# easyMySens-Std-V2-021.net
KiCad netlist of a schematic drawn in EAGLE
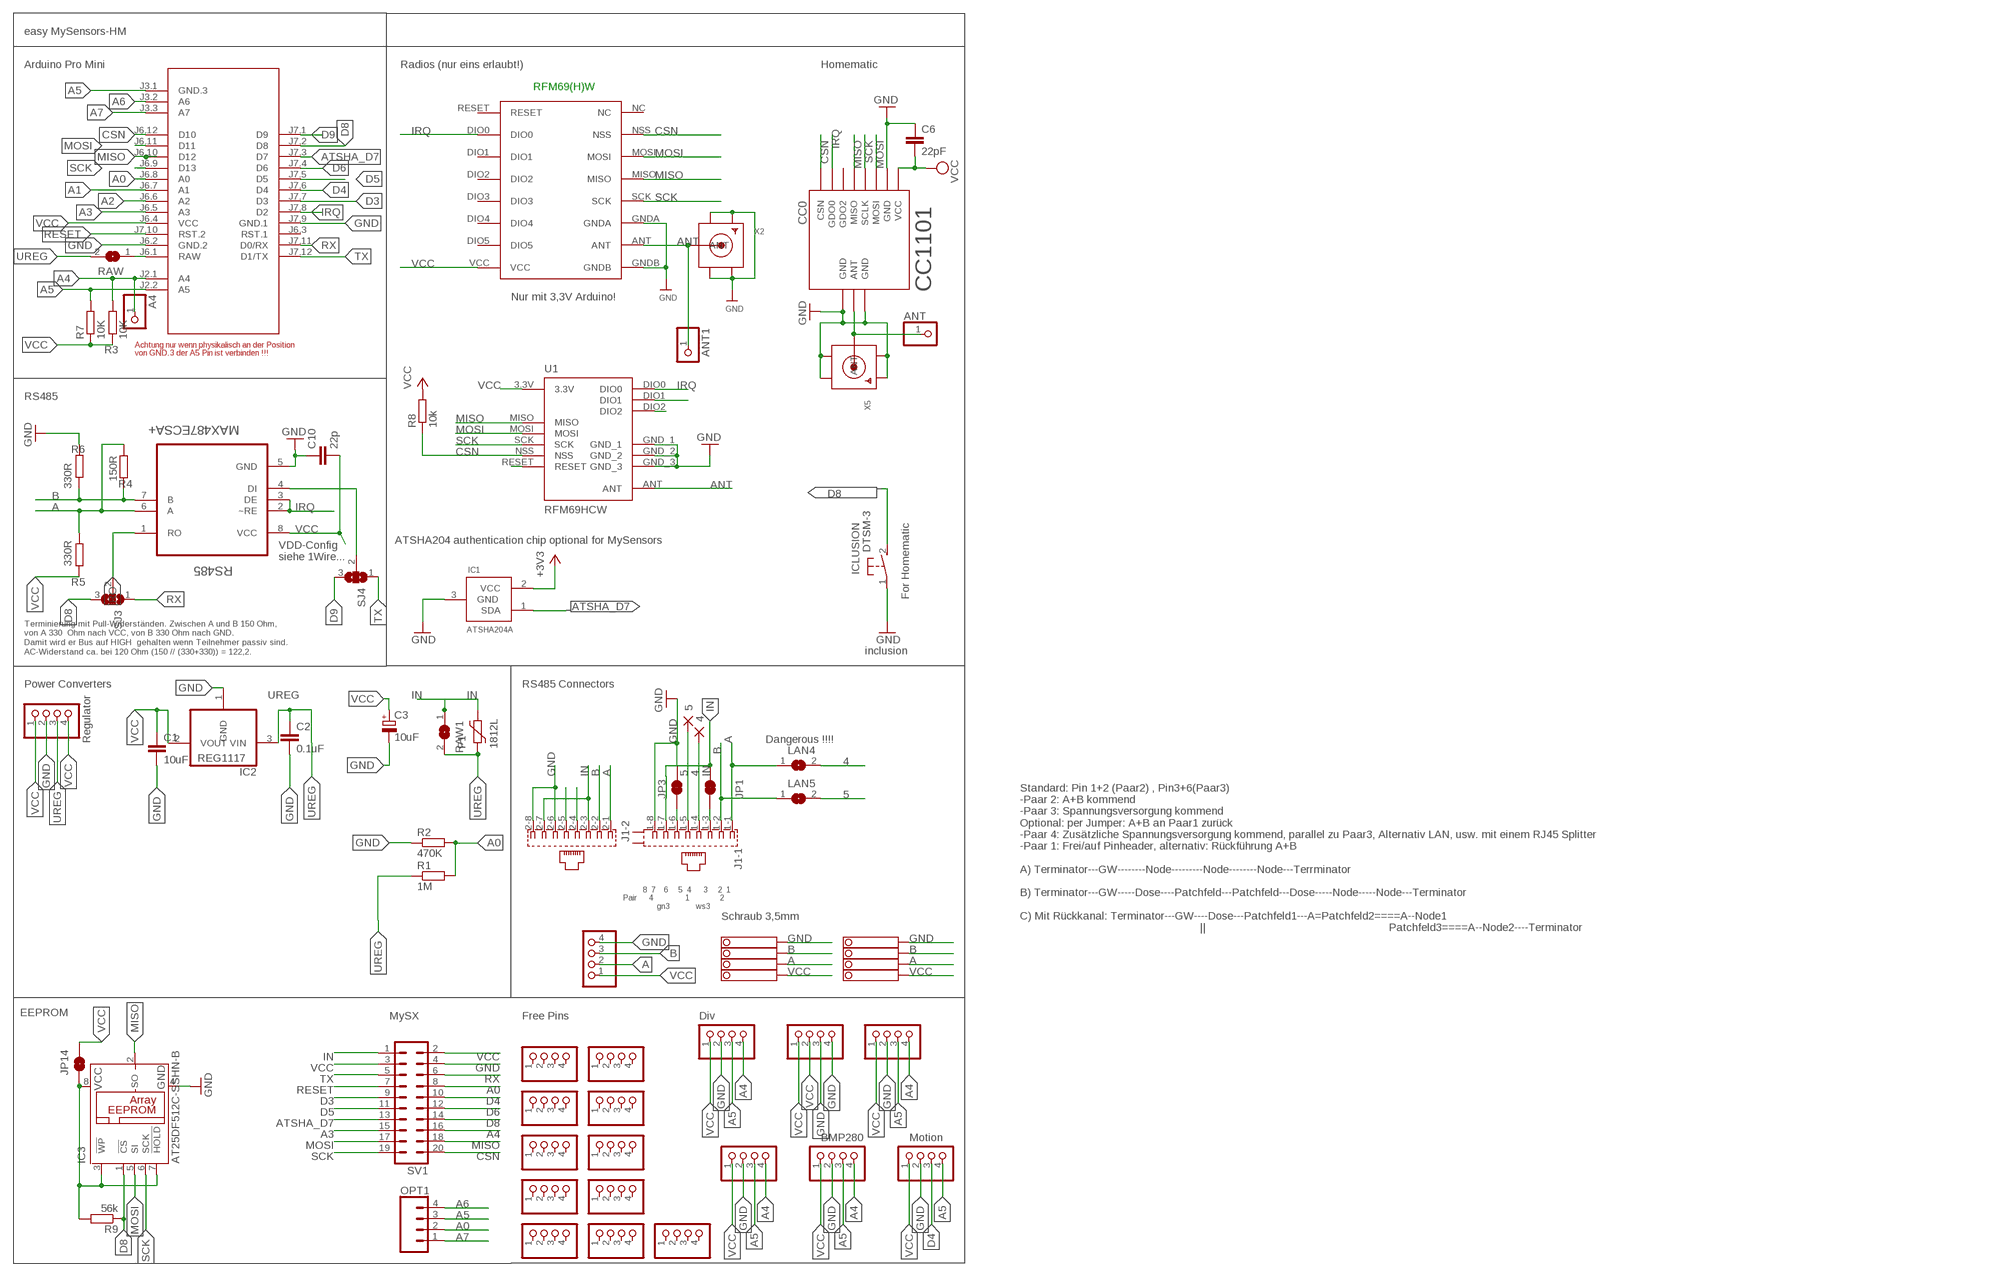
[diagram p0: schematic, sheet 1]

(export (version "E")
  (design (tool "Eeschema 10.0.6"))
  (components
    (comp (ref "4")
      (value "1,6/0,8")
      (footprint "eagle-import:1,6_0,8")
      (libsource (lib "eagle-import") (part "1,6/0,8"))
    )
    (comp (ref "5")
      (value "1,6/0,8")
      (footprint "eagle-import:1,6_0,8")
      (libsource (lib "eagle-import") (part "1,6/0,8"))
    )
    (comp (ref "A4")
      (value "PINHD-1X1")
      (footprint "eagle-import:1X01")
      (libsource (lib "eagle-import") (part "PINHD-1X1"))
    )
    (comp (ref "ANT")
      (value "PINHD-1X1")
      (footprint "eagle-import:1X01")
      (libsource (lib "eagle-import") (part "PINHD-1X1"))
    )
    (comp (ref "ANT1")
      (value "PINHD-1X1")
      (footprint "eagle-import:1X01")
      (libsource (lib "eagle-import") (part "PINHD-1X1"))
    )
    (comp (ref "BH1750")
      (value "PINHD-1X04_2.54-S")
      (footprint "eagle-import:1X04-S")
      (libsource (lib "eagle-import") (part "PINHD-1X04_2.54-S"))
    )
    (comp (ref "C1")
      (value "10uF")
      (footprint "eagle-import:C1210")
      (libsource (lib "eagle-import") (part "C-EUC1210"))
    )
    (comp (ref "C2")
      (value "0.1uF")
      (footprint "eagle-import:C1206")
      (libsource (lib "eagle-import") (part "C-EUC1206"))
    )
    (comp (ref "C3")
      (value "10uF")
      (footprint "eagle-import:SMC_C")
      (libsource (lib "eagle-import") (part "CPOL-EUSMCC"))
    )
    (comp (ref "C6")
      (value "22pF")
      (footprint "eagle-import:C0805")
      (libsource (lib "eagle-import") (part "C-EUC0805"))
    )
    (comp (ref "C10")
      (value "22p")
      (footprint "eagle-import:C0805")
      (libsource (lib "eagle-import") (part "C-EUC0805"))
    )
    (comp (ref "CC0")
      (value "CC1101")
      (footprint "eagle-import:CC1101_MODULE1_SMD")
      (libsource (lib "eagle-import") (part "CC1101_MODULE1SMD"))
    )
    (comp (ref "F1")
      (value "1812L")
      (footprint "eagle-import:1812L")
      (libsource (lib "eagle-import") (part "1812L"))
    )
    (comp (ref "I2C-1")
      (value "PINHD-1X04_2.54-S")
      (footprint "eagle-import:1X04-S")
      (libsource (lib "eagle-import") (part "PINHD-1X04_2.54-S"))
    )
    (comp (ref "I2C-2")
      (value "PINHD-1X04_2.54-S")
      (footprint "eagle-import:1X04-S")
      (libsource (lib "eagle-import") (part "PINHD-1X04_2.54-S"))
    )
    (comp (ref "I2C-3")
      (value "PINHD-1X04_2.54-S")
      (footprint "eagle-import:1X04-S")
      (libsource (lib "eagle-import") (part "PINHD-1X04_2.54-S"))
    )
    (comp (ref "I2C-4")
      (value "PINHD-1X04_2.54-S")
      (footprint "eagle-import:1X04-S")
      (libsource (lib "eagle-import") (part "PINHD-1X04_2.54-S"))
    )
    (comp (ref "IC1")
      (value "ATSHA204A")
      (footprint "eagle-import:SOT23")
      (libsource (lib "eagle-import") (part "ATSHA204A"))
    )
    (comp (ref "IC2")
      (value "REG1117")
      (footprint "eagle-import:SOT223")
      (libsource (lib "eagle-import") (part "REG1117"))
    )
    (comp (ref "IC3")
      (value "AT25DF512C-SSHN-B")
      (footprint "eagle-import:SO-08")
      (fields (field (name "MF") "MICROCHIP") (field (name "MPN") "25AA080/SN"))
      (libsource (lib "eagle-import") (part "25SNAA080"))
    )
    (comp (ref "ICLUSION")
      (value "DTSM-3")
      (footprint "eagle-import:DTSM-3")
      (libsource (lib "eagle-import") (part "DTSM-3"))
    )
    (comp (ref "J1")
      (value "557570-1")
      (footprint "eagle-import:557570-1")
      (libsource (lib "eagle-import") (part "557570-1"))
    )
    (comp (ref "JP1")
      (value "JUMPER-SMT_2_NC_TRACE_SILK")
      (footprint "eagle-import:SMT-JUMPER_2_NC_TRACE_SILK")
      (libsource (lib "eagle-import") (part "JUMPER-SMT_2_NC_TRACE_SILK"))
    )
    (comp (ref "JP2")
      (value "PINHD-1X04_2.54-S")
      (footprint "eagle-import:1X04-S")
      (libsource (lib "eagle-import") (part "PINHD-1X04_2.54-S"))
    )
    (comp (ref "JP3")
      (value "JUMPER-SMT_2_NC_TRACE_SILK")
      (footprint "eagle-import:SMT-JUMPER_2_NC_TRACE_SILK")
      (libsource (lib "eagle-import") (part "JUMPER-SMT_2_NC_TRACE_SILK"))
    )
    (comp (ref "JP4")
      (value "PINHD-1X04_2.54-S")
      (footprint "eagle-import:1X04-S")
      (libsource (lib "eagle-import") (part "PINHD-1X04_2.54-S"))
    )
    (comp (ref "JP5")
      (value "PINHD-1X04_2.54-S")
      (footprint "eagle-import:1X04-S")
      (libsource (lib "eagle-import") (part "PINHD-1X04_2.54-S"))
    )
    (comp (ref "JP6")
      (value "PINHD-1X04_2.54-S")
      (footprint "eagle-import:1X04-S")
      (libsource (lib "eagle-import") (part "PINHD-1X04_2.54-S"))
    )
    (comp (ref "JP7")
      (value "PINHD-1X04_2.54-S")
      (footprint "eagle-import:1X04-S")
      (libsource (lib "eagle-import") (part "PINHD-1X04_2.54-S"))
    )
    (comp (ref "JP8")
      (value "PINHD-1X04_2.54-S")
      (footprint "eagle-import:1X04-S")
      (libsource (lib "eagle-import") (part "PINHD-1X04_2.54-S"))
    )
    (comp (ref "JP9")
      (value "PINHD-1X04_2.54-S")
      (footprint "eagle-import:1X04-S")
      (libsource (lib "eagle-import") (part "PINHD-1X04_2.54-S"))
    )
    (comp (ref "JP10")
      (value "PINHD-1X04_2.54-S")
      (footprint "eagle-import:1X04-S")
      (libsource (lib "eagle-import") (part "PINHD-1X04_2.54-S"))
    )
    (comp (ref "JP11")
      (value "PINHD-1X04_2.54-S")
      (footprint "eagle-import:1X04-S")
      (libsource (lib "eagle-import") (part "PINHD-1X04_2.54-S"))
    )
    (comp (ref "JP12")
      (value "PINHD-1X04_2.54-S")
      (footprint "eagle-import:1X04-S")
      (libsource (lib "eagle-import") (part "PINHD-1X04_2.54-S"))
    )
    (comp (ref "JP13")
      (value "PINHD-1X04_2.54-S")
      (footprint "eagle-import:1X04-S")
      (libsource (lib "eagle-import") (part "PINHD-1X04_2.54-S"))
    )
    (comp (ref "JP14")
      (value "JUMPER-SMT_2_NC_TRACE_SILK")
      (footprint "eagle-import:SMT-JUMPER_2_NC_TRACE_SILK")
      (libsource (lib "eagle-import") (part "JUMPER-SMT_2_NC_TRACE_SILK"))
    )
    (comp (ref "LAN4")
      (value "SJ")
      (footprint "eagle-import:SJ")
      (libsource (lib "eagle-import") (part "SJ"))
    )
    (comp (ref "LAN5")
      (value "SJ")
      (footprint "eagle-import:SJ")
      (libsource (lib "eagle-import") (part "SJ"))
    )
    (comp (ref "M1")
      (value "ARDUINO-PRO-MINI-3.3V#NP")
      (footprint "eagle-import:ARDUINO-PRO-MINI#NP")
      (libsource (lib "eagle-import") (part "ARDUINO-PRO-MINI-#NP3.3V"))
    )
    (comp (ref "MOTION")
      (value "PINHD-1X04_2.54-S")
      (footprint "eagle-import:1X04-S")
      (libsource (lib "eagle-import") (part "PINHD-1X04_2.54-S"))
    )
    (comp (ref "OPT1")
      (value "CONN_04")
      (footprint "eagle-import:1X04")
      (libsource (lib "eagle-import") (part "CONN_04"))
    )
    (comp (ref "R1")
      (value "1M")
      (footprint "eagle-import:R0805")
      (libsource (lib "eagle-import") (part "R-EU_R0805"))
    )
    (comp (ref "R2")
      (value "470K")
      (footprint "eagle-import:R0805")
      (libsource (lib "eagle-import") (part "R-EU_R0805"))
    )
    (comp (ref "R3")
      (value "10K")
      (footprint "eagle-import:R0805")
      (libsource (lib "eagle-import") (part "R-EU_R0805"))
    )
    (comp (ref "R4")
      (value "150R")
      (footprint "eagle-import:R0805")
      (libsource (lib "eagle-import") (part "R-EU_R0805"))
    )
    (comp (ref "R5")
      (value "330R")
      (footprint "eagle-import:R0805")
      (libsource (lib "eagle-import") (part "R-EU_R0805"))
    )
    (comp (ref "R6")
      (value "330R")
      (footprint "eagle-import:R0805")
      (libsource (lib "eagle-import") (part "R-EU_R0805"))
    )
    (comp (ref "R7")
      (value "10K")
      (footprint "eagle-import:R0805")
      (libsource (lib "eagle-import") (part "R-EU_R0805"))
    )
    (comp (ref "R8")
      (value "10k")
      (footprint "eagle-import:M0805")
      (libsource (lib "eagle-import") (part "R-EU_M0805"))
    )
    (comp (ref "R9")
      (value "56k")
      (footprint "eagle-import:M0805")
      (libsource (lib "eagle-import") (part "resistor_R-EU_M0805"))
    )
    (comp (ref "RAW") (value "SJ") (footprint "eagle-import:SJ") (libsource (lib "eagle-import") (part "SJ")))
    (comp (ref "RAW1")
      (value "SJ")
      (footprint "eagle-import:SJ")
      (libsource (lib "eagle-import") (part "SJ"))
    )
    (comp (ref "RFM69W")
      (value "RFM69HW")
      (footprint "eagle-import:RFM")
      (libsource (lib "eagle-import") (part "RFM69HW"))
    )
    (comp (ref "RS485")
      (value "MAX487ECSA+")
      (footprint "eagle-import:SOIC127P600X175-8N")
      (libsource (lib "eagle-import") (part "MAX487ECSA+"))
    )
    (comp (ref "RS485-")
      (value "PINHD-1X04_2.54-S")
      (footprint "eagle-import:1X04-S")
      (libsource (lib "eagle-import") (part "PINHD-1X04_2.54-S"))
    )
    (comp (ref "SJ3")
      (value "SJ2W")
      (footprint "eagle-import:SJ_2")
      (libsource (lib "eagle-import") (part "SJ2W"))
    )
    (comp (ref "SJ4")
      (value "SJ2W")
      (footprint "eagle-import:SJ_2")
      (libsource (lib "eagle-import") (part "SJ2W"))
    )
    (comp (ref "STEPDWN")
      (value "PINHD-1X04_2.54-S")
      (footprint "eagle-import:1X04-S")
      (libsource (lib "eagle-import") (part "PINHD-1X04_2.54-S"))
    )
    (comp (ref "SV1")
      (value "MA10-2")
      (footprint "eagle-import:MA10-2")
      (libsource (lib "eagle-import") (part "MA10-2"))
    )
    (comp (ref "U1")
      (value "RFM69HCW")
      (footprint "eagle-import:RFM69HCW-XXXS2")
      (libsource (lib "eagle-import") (part "RFM69HCW"))
    )
    (comp (ref "X1")
      (value "1751264")
      (footprint "eagle-import:1751264")
      (libsource (lib "eagle-import") (part "1751264"))
    )
    (comp (ref "X2")
      (value "SMACONNECTOR_EDGE")
      (footprint "eagle-import:SMA_EDGELAUNCH")
      (libsource (lib "eagle-import") (part "SMACONNECTOR_EDGE"))
    )
    (comp (ref "X4")
      (value "1751264")
      (footprint "eagle-import:1751264")
      (libsource (lib "eagle-import") (part "1751264"))
    )
    (comp (ref "X5")
      (value "SMACONNECTOR_EDGE")
      (footprint "eagle-import:SMA_EDGELAUNCH")
      (libsource (lib "eagle-import") (part "SMACONNECTOR_EDGE"))
    )
  )
  (nets
    (net (code "1") (name "+3V3") (class "Default")
      (node (ref "IC1") (pin "2") (pinfunction "VCC_2") (pintype "bidirectional"))
    )
    (net (code "2") (name "/4") (class "Default")
      (node (ref "4") (pin "1") (pinfunction "P_1") (pintype "passive"))
      (node (ref "J1") (pin "1-4") (pinfunction "4_1-4") (pintype "passive"))
      (node (ref "LAN4") (pin "2") (pinfunction "2_2") (pintype "passive"))
    )
    (net (code "3") (name "/5") (class "Default")
      (node (ref "5") (pin "1") (pinfunction "P_1") (pintype "passive"))
      (node (ref "J1") (pin "1-5") (pinfunction "5_1-5") (pintype "passive"))
      (node (ref "LAN5") (pin "2") (pinfunction "2_2") (pintype "passive"))
    )
    (net (code "4") (name "/ANT") (class "Default")
      (node (ref "ANT1") (pin "1") (pinfunction "1_1") (pintype "passive"))
      (node (ref "RFM69W") (pin "ANT") (pinfunction "ANT_ANT") (pintype "bidirectional"))
      (node (ref "U1") (pin "ANT") (pinfunction "ANT_ANT") (pintype "passive"))
      (node (ref "X2") (pin "P") (pinfunction "ANT_P") (pintype "bidirectional"))
    )
    (net (code "5") (name "A") (class "Default")
      (node (ref "J1") (pin "1-1") (pinfunction "1_1-1") (pintype "passive"))
      (node (ref "J1") (pin "2-1") (pinfunction "1_2-1") (pintype "passive"))
      (node (ref "LAN4") (pin "1") (pinfunction "1_1") (pintype "passive"))
      (node (ref "R4") (pin "1") (pinfunction "1_1") (pintype "passive"))
      (node (ref "R5") (pin "2") (pinfunction "2_2") (pintype "passive"))
      (node (ref "RS485") (pin "6") (pinfunction "A_6") (pintype "bidirectional"))
      (node (ref "RS485-") (pin "2") (pinfunction "2_2") (pintype "passive"))
      (node (ref "X1") (pin "2") (pinfunction "K_2") (pintype "passive"))
      (node (ref "X4") (pin "2") (pinfunction "K_2") (pintype "passive"))
    )
    (net (code "6") (name "A0") (class "Default")
      (node (ref "M1") (pin "J6.8") (pinfunction "A0_J6.8") (pintype "bidirectional"))
      (node (ref "OPT1") (pin "2") (pinfunction "2_2") (pintype "passive"))
      (node (ref "R1") (pin "2") (pinfunction "2_2") (pintype "passive"))
      (node (ref "R2") (pin "2") (pinfunction "2_2") (pintype "passive"))
      (node (ref "SV1") (pin "8") (pinfunction "8_8") (pintype "passive"))
    )
    (net (code "7") (name "A1") (class "Default")
      (node (ref "M1") (pin "J6.7") (pinfunction "A1_J6.7") (pintype "bidirectional"))
    )
    (net (code "8") (name "A2") (class "Default")
      (node (ref "M1") (pin "J6.6") (pinfunction "A2_J6.6") (pintype "bidirectional"))
    )
    (net (code "9") (name "A3") (class "Default")
      (node (ref "M1") (pin "J6.5") (pinfunction "A3_J6.5") (pintype "bidirectional"))
      (node (ref "SV1") (pin "15") (pinfunction "15_15") (pintype "passive"))
    )
    (net (code "10") (name "A4") (class "Default")
      (node (ref "A4") (pin "1") (pinfunction "1_1") (pintype "passive"))
      (node (ref "BH1750") (pin "4") (pinfunction "4_4") (pintype "passive"))
      (node (ref "I2C-1") (pin "4") (pinfunction "4_4") (pintype "passive"))
      (node (ref "I2C-2") (pin "4") (pinfunction "4_4") (pintype "passive"))
      (node (ref "I2C-4") (pin "4") (pinfunction "4_4") (pintype "passive"))
      (node (ref "M1") (pin "J2.1") (pinfunction "A4_J2.1") (pintype "bidirectional"))
      (node (ref "R3") (pin "2") (pinfunction "2_2") (pintype "passive"))
      (node (ref "SV1") (pin "16") (pinfunction "16_16") (pintype "passive"))
    )
    (net (code "11") (name "A5") (class "Default")
      (node (ref "BH1750") (pin "3") (pinfunction "3_3") (pintype "passive"))
      (node (ref "I2C-1") (pin "3") (pinfunction "3_3") (pintype "passive"))
      (node (ref "I2C-2") (pin "3") (pinfunction "3_3") (pintype "passive"))
      (node (ref "I2C-4") (pin "3") (pinfunction "3_3") (pintype "passive"))
      (node (ref "M1") (pin "J2.2") (pinfunction "A5_J2.2") (pintype "bidirectional"))
      (node (ref "M1") (pin "J3.1") (pinfunction "GND.3_J3.1") (pintype "bidirectional"))
      (node (ref "MOTION") (pin "4") (pinfunction "4_4") (pintype "passive"))
      (node (ref "OPT1") (pin "3") (pinfunction "3_3") (pintype "passive"))
      (node (ref "R7") (pin "2") (pinfunction "2_2") (pintype "passive"))
    )
    (net (code "12") (name "A6") (class "Default")
      (node (ref "M1") (pin "J3.2") (pinfunction "A6_J3.2") (pintype "bidirectional"))
      (node (ref "OPT1") (pin "4") (pinfunction "4_4") (pintype "passive"))
    )
    (net (code "13") (name "A7") (class "Default")
      (node (ref "M1") (pin "J3.3") (pinfunction "A7_J3.3") (pintype "bidirectional"))
      (node (ref "OPT1") (pin "1") (pinfunction "1_1") (pintype "passive"))
    )
    (net (code "14") (name "ATSHA_D7") (class "Default")
      (node (ref "IC1") (pin "1") (pinfunction "SDA_1") (pintype "bidirectional"))
      (node (ref "M1") (pin "J7.3") (pinfunction "D7_J7.3") (pintype "bidirectional"))
      (node (ref "SV1") (pin "13") (pinfunction "13_13") (pintype "passive"))
    )
    (net (code "15") (name "B") (class "Default")
      (node (ref "J1") (pin "1-2") (pinfunction "2_1-2") (pintype "passive"))
      (node (ref "J1") (pin "2-2") (pinfunction "2_2-2") (pintype "passive"))
      (node (ref "LAN5") (pin "1") (pinfunction "1_1") (pintype "passive"))
      (node (ref "R4") (pin "2") (pinfunction "2_2") (pintype "passive"))
      (node (ref "R6") (pin "1") (pinfunction "1_1") (pintype "passive"))
      (node (ref "RS485") (pin "7") (pinfunction "B_7") (pintype "bidirectional"))
      (node (ref "RS485-") (pin "3") (pinfunction "3_3") (pintype "passive"))
      (node (ref "X1") (pin "3") (pinfunction "K_3") (pintype "passive"))
      (node (ref "X4") (pin "3") (pinfunction "K_3") (pintype "passive"))
    )
    (net (code "16") (name "CSN") (class "Default")
      (node (ref "CC0") (pin "CSN") (pinfunction "CSN_CSN") (pintype "bidirectional"))
      (node (ref "M1") (pin "J6.12") (pinfunction "D10_J6.12") (pintype "bidirectional"))
      (node (ref "R8") (pin "1") (pinfunction "1_1") (pintype "passive"))
      (node (ref "RFM69W") (pin "NSS") (pinfunction "NSS_NSS") (pintype "bidirectional"))
      (node (ref "SV1") (pin "20") (pinfunction "20_20") (pintype "passive"))
      (node (ref "U1") (pin "NSS") (pinfunction "NSS_NSS") (pintype "input"))
    )
    (net (code "17") (name "D3") (class "Default")
      (node (ref "M1") (pin "J7.7") (pinfunction "D3_J7.7") (pintype "bidirectional"))
      (node (ref "SV1") (pin "9") (pinfunction "9_9") (pintype "passive"))
    )
    (net (code "18") (name "D4") (class "Default")
      (node (ref "M1") (pin "J7.6") (pinfunction "D4_J7.6") (pintype "bidirectional"))
      (node (ref "MOTION") (pin "3") (pinfunction "3_3") (pintype "passive"))
      (node (ref "SV1") (pin "10") (pinfunction "10_10") (pintype "passive"))
    )
    (net (code "19") (name "D5") (class "Default")
      (node (ref "M1") (pin "J7.5") (pinfunction "D5_J7.5") (pintype "bidirectional"))
      (node (ref "SV1") (pin "11") (pinfunction "11_11") (pintype "passive"))
    )
    (net (code "20") (name "D6") (class "Default")
      (node (ref "M1") (pin "J7.4") (pinfunction "D6_J7.4") (pintype "bidirectional"))
      (node (ref "SV1") (pin "12") (pinfunction "12_12") (pintype "passive"))
    )
    (net (code "21") (name "D8") (class "Default")
      (node (ref "IC3") (pin "1") (pinfunction "~{CS}_1") (pintype "input"))
      (node (ref "ICLUSION") (pin "2") (pinfunction "2_2") (pintype "passive"))
      (node (ref "M1") (pin "J7.2") (pinfunction "D8_J7.2") (pintype "bidirectional"))
      (node (ref "R9") (pin "1") (pinfunction "1_1") (pintype "passive"))
      (node (ref "SJ3") (pin "3") (pinfunction "3_3") (pintype "passive"))
      (node (ref "SV1") (pin "14") (pinfunction "14_14") (pintype "passive"))
    )
    (net (code "22") (name "D9") (class "Default")
      (node (ref "M1") (pin "J7.1") (pinfunction "D9_J7.1") (pintype "bidirectional"))
      (node (ref "SJ4") (pin "3") (pinfunction "3_3") (pintype "passive"))
    )
    (net (code "23") (name "GND") (class "Default")
      (node (ref "BH1750") (pin "2") (pinfunction "2_2") (pintype "passive"))
      (node (ref "C1") (pin "2") (pinfunction "2_2") (pintype "passive"))
      (node (ref "C10") (pin "1") (pinfunction "1_1") (pintype "passive"))
      (node (ref "C2") (pin "2") (pinfunction "2_2") (pintype "passive"))
      (node (ref "C3") (pin "-") (pinfunction "-_-") (pintype "passive"))
      (node (ref "C6") (pin "1") (pinfunction "1_1") (pintype "passive"))
      (node (ref "CC0") (pin "GND@0") (pinfunction "GND_GND@0") (pintype "power_in"))
      (node (ref "CC0") (pin "GND@1") (pinfunction "GND_GND@1") (pintype "power_in"))
      (node (ref "CC0") (pin "GND@2") (pinfunction "GND_GND@2") (pintype "power_in"))
      (node (ref "I2C-1") (pin "2") (pinfunction "2_2") (pintype "passive"))
      (node (ref "I2C-2") (pin "2") (pinfunction "2_2") (pintype "passive"))
      (node (ref "I2C-3") (pin "3") (pinfunction "3_3") (pintype "passive"))
      (node (ref "I2C-3") (pin "4") (pinfunction "4_4") (pintype "passive"))
      (node (ref "I2C-4") (pin "2") (pinfunction "2_2") (pintype "passive"))
      (node (ref "IC1") (pin "3") (pinfunction "GND_3") (pintype "bidirectional"))
      (node (ref "IC2") (pin "1") (pinfunction "GND_1") (pintype "power_in"))
      (node (ref "IC3") (pin "4") (pinfunction "GND_4") (pintype "power_in"))
      (node (ref "ICLUSION") (pin "1") (pinfunction "1_1") (pintype "passive"))
      (node (ref "J1") (pin "1-8") (pinfunction "8_1-8") (pintype "passive"))
      (node (ref "J1") (pin "2-6") (pinfunction "6_2-6") (pintype "passive"))
      (node (ref "J1") (pin "2-8") (pinfunction "8_2-8") (pintype "passive"))
      (node (ref "JP3") (pin "2") (pinfunction "2_2") (pintype "passive"))
      (node (ref "M1") (pin "J6.2") (pinfunction "GND.2_J6.2") (pintype "power_in"))
      (node (ref "M1") (pin "J7.9") (pinfunction "GND.1_J7.9") (pintype "power_in"))
      (node (ref "MOTION") (pin "2") (pinfunction "2_2") (pintype "passive"))
      (node (ref "R2") (pin "1") (pinfunction "1_1") (pintype "passive"))
      (node (ref "R6") (pin "2") (pinfunction "2_2") (pintype "passive"))
      (node (ref "RFM69W") (pin "GNDA") (pinfunction "GNDA_GNDA") (pintype "bidirectional"))
      (node (ref "RFM69W") (pin "GNDB") (pinfunction "GNDB_GNDB") (pintype "bidirectional"))
      (node (ref "RS485") (pin "5") (pinfunction "GND_5") (pintype "passive"))
      (node (ref "RS485-") (pin "4") (pinfunction "4_4") (pintype "passive"))
      (node (ref "STEPDWN") (pin "2") (pinfunction "2_2") (pintype "passive"))
      (node (ref "SV1") (pin "4") (pinfunction "4_4") (pintype "passive"))
      (node (ref "U1") (pin "GND_1") (pinfunction "GND_1_GND_1") (pintype "power_in"))
      (node (ref "U1") (pin "GND_2") (pinfunction "GND_2_GND_2") (pintype "power_in"))
      (node (ref "U1") (pin "GND_3") (pinfunction "GND_3_GND_3") (pintype "power_in"))
      (node (ref "X1") (pin "4") (pinfunction "K_4") (pintype "passive"))
      (node (ref "X2") (pin "GND@1") (pinfunction "GND4_GND@1") (pintype "power_in"))
      (node (ref "X2") (pin "GND@2") (pinfunction "GND3_GND@2") (pintype "power_in"))
      (node (ref "X2") (pin "GND@3") (pinfunction "GND2_GND@3") (pintype "power_in"))
      (node (ref "X2") (pin "GND@4") (pinfunction "GND1_GND@4") (pintype "power_in"))
      (node (ref "X4") (pin "4") (pinfunction "K_4") (pintype "passive"))
      (node (ref "X5") (pin "GND@1") (pinfunction "GND4_GND@1") (pintype "power_in"))
      (node (ref "X5") (pin "GND@2") (pinfunction "GND3_GND@2") (pintype "power_in"))
      (node (ref "X5") (pin "GND@3") (pinfunction "GND2_GND@3") (pintype "power_in"))
      (node (ref "X5") (pin "GND@4") (pinfunction "GND1_GND@4") (pintype "power_in"))
    )
    (net (code "24") (name "IN") (class "Default")
      (node (ref "F1") (pin "P$2") (pinfunction "2_P$2") (pintype "passive"))
      (node (ref "J1") (pin "1-7") (pinfunction "7_1-7") (pintype "passive"))
      (node (ref "J1") (pin "2-3") (pinfunction "3_2-3") (pintype "passive"))
      (node (ref "J1") (pin "2-7") (pinfunction "7_2-7") (pintype "passive"))
      (node (ref "JP1") (pin "2") (pinfunction "2_2") (pintype "passive"))
      (node (ref "RAW1") (pin "1") (pinfunction "1_1") (pintype "passive"))
      (node (ref "SV1") (pin "1") (pinfunction "1_1") (pintype "passive"))
    )
    (net (code "25") (name "IRQ") (class "Default")
      (node (ref "CC0") (pin "GDO0") (pinfunction "GDO0_GDO0") (pintype "bidirectional"))
      (node (ref "M1") (pin "J7.8") (pinfunction "D2_J7.8") (pintype "bidirectional"))
      (node (ref "RFM69W") (pin "DIO0") (pinfunction "DIO0_DIO0") (pintype "bidirectional"))
      (node (ref "RS485") (pin "2") (pinfunction "~{RE}_2") (pintype "input"))
      (node (ref "RS485") (pin "3") (pinfunction "DE_3") (pintype "input"))
      (node (ref "U1") (pin "DIO0") (pinfunction "DIO0_DIO0") (pintype "bidirectional"))
    )
    (net (code "26") (name "MISO") (class "Default")
      (node (ref "CC0") (pin "MISO") (pinfunction "MISO_MISO") (pintype "bidirectional"))
      (node (ref "IC3") (pin "2") (pinfunction "SO_2") (pintype "bidirectional"))
      (node (ref "M1") (pin "J6.10") (pinfunction "D12_J6.10") (pintype "bidirectional"))
      (node (ref "RFM69W") (pin "MISO") (pinfunction "MISO_MISO") (pintype "bidirectional"))
      (node (ref "SV1") (pin "18") (pinfunction "18_18") (pintype "passive"))
      (node (ref "U1") (pin "MISO") (pinfunction "MISO_MISO") (pintype "bidirectional"))
    )
    (net (code "27") (name "MOSI") (class "Default")
      (node (ref "CC0") (pin "MOSI") (pinfunction "MOSI_MOSI") (pintype "bidirectional"))
      (node (ref "IC3") (pin "5") (pinfunction "SI_5") (pintype "input"))
      (node (ref "M1") (pin "J6.11") (pinfunction "D11_J6.11") (pintype "bidirectional"))
      (node (ref "RFM69W") (pin "MOSI") (pinfunction "MOSI_MOSI") (pintype "bidirectional"))
      (node (ref "SV1") (pin "17") (pinfunction "17_17") (pintype "passive"))
      (node (ref "U1") (pin "MOSI") (pinfunction "MOSI_MOSI") (pintype "input"))
    )
    (net (code "28") (name "Net-(IC3-VCC)") (class "Default")
      (node (ref "IC3") (pin "3") (pinfunction "~{WP}_3") (pintype "input"))
      (node (ref "IC3") (pin "7") (pinfunction "~{HOLD}_7") (pintype "input"))
      (node (ref "IC3") (pin "8") (pinfunction "VCC_8") (pintype "power_in"))
      (node (ref "JP14") (pin "1") (pinfunction "1_1") (pintype "passive"))
      (node (ref "R9") (pin "2") (pinfunction "2_2") (pintype "passive"))
    )
    (net (code "29") (name "Net-(J1A-3)") (class "Default")
      (node (ref "J1") (pin "1-3") (pinfunction "3_1-3") (pintype "passive"))
      (node (ref "JP1") (pin "1") (pinfunction "1_1") (pintype "passive"))
    )
    (net (code "30") (name "Net-(J1A-6)") (class "Default")
      (node (ref "J1") (pin "1-6") (pinfunction "6_1-6") (pintype "passive"))
      (node (ref "JP3") (pin "1") (pinfunction "1_1") (pintype "passive"))
    )
    (net (code "31") (name "Net-(M1-RAW)") (class "Default")
      (node (ref "M1") (pin "J6.1") (pinfunction "RAW_J6.1") (pintype "power_in"))
      (node (ref "RAW") (pin "1") (pinfunction "1_1") (pintype "passive"))
    )
    (net (code "32") (name "Net-(RS485-DI)") (class "Default")
      (node (ref "RS485") (pin "4") (pinfunction "DI_4") (pintype "input"))
      (node (ref "SJ4") (pin "2") (pinfunction "2_2") (pintype "passive"))
    )
    (net (code "33") (name "Net-(X5-ANT)") (class "Default")
      (node (ref "ANT") (pin "1") (pinfunction "1_1") (pintype "passive"))
      (node (ref "CC0") (pin "ANT") (pinfunction "ANT_ANT") (pintype "output"))
      (node (ref "X5") (pin "P") (pinfunction "ANT_P") (pintype "bidirectional"))
    )
    (net (code "34") (name "RESET") (class "Default")
      (node (ref "M1") (pin "J7.10") (pinfunction "RST.2_J7.10") (pintype "bidirectional"))
      (node (ref "SV1") (pin "7") (pinfunction "7_7") (pintype "passive"))
    )
    (net (code "35") (name "RO") (class "Default")
      (node (ref "RS485") (pin "1") (pinfunction "RO_1") (pintype "output"))
      (node (ref "SJ3") (pin "2") (pinfunction "2_2") (pintype "passive"))
    )
    (net (code "36") (name "RX") (class "Default")
      (node (ref "M1") (pin "J7.11") (pinfunction "D0/RX_J7.11") (pintype "bidirectional"))
      (node (ref "SJ3") (pin "1") (pinfunction "1_1") (pintype "passive"))
      (node (ref "SV1") (pin "6") (pinfunction "6_6") (pintype "passive"))
    )
    (net (code "37") (name "SCK") (class "Default")
      (node (ref "CC0") (pin "SCLK") (pinfunction "SCLK_SCLK") (pintype "bidirectional"))
      (node (ref "IC3") (pin "6") (pinfunction "SCK_6") (pintype "input"))
      (node (ref "M1") (pin "J6.9") (pinfunction "D13_J6.9") (pintype "bidirectional"))
      (node (ref "RFM69W") (pin "SCK") (pinfunction "SCK_SCK") (pintype "bidirectional"))
      (node (ref "SV1") (pin "19") (pinfunction "19_19") (pintype "passive"))
      (node (ref "U1") (pin "SCK") (pinfunction "SCK_SCK") (pintype "input"))
    )
    (net (code "38") (name "TX") (class "Default")
      (node (ref "M1") (pin "J7.12") (pinfunction "D1/TX_J7.12") (pintype "bidirectional"))
      (node (ref "SJ4") (pin "1") (pinfunction "1_1") (pintype "passive"))
      (node (ref "SV1") (pin "5") (pinfunction "5_5") (pintype "passive"))
    )
    (net (code "39") (name "UREG") (class "Default")
      (node (ref "C2") (pin "1") (pinfunction "1_1") (pintype "passive"))
      (node (ref "F1") (pin "P$1") (pinfunction "1_P$1") (pintype "passive"))
      (node (ref "IC2") (pin "3") (pinfunction "VIN_3") (pintype "input"))
      (node (ref "R1") (pin "1") (pinfunction "1_1") (pintype "passive"))
      (node (ref "RAW") (pin "2") (pinfunction "2_2") (pintype "passive"))
      (node (ref "RAW1") (pin "2") (pinfunction "2_2") (pintype "passive"))
      (node (ref "STEPDWN") (pin "3") (pinfunction "3_3") (pintype "passive"))
    )
    (net (code "40") (name "VCC") (class "Default")
      (node (ref "BH1750") (pin "1") (pinfunction "1_1") (pintype "passive"))
      (node (ref "C1") (pin "1") (pinfunction "1_1") (pintype "passive"))
      (node (ref "C10") (pin "2") (pinfunction "2_2") (pintype "passive"))
      (node (ref "C3") (pin "+") (pinfunction "+_+") (pintype "passive"))
      (node (ref "C6") (pin "2") (pinfunction "2_2") (pintype "passive"))
      (node (ref "CC0") (pin "VCC") (pinfunction "VCC_VCC") (pintype "power_in"))
      (node (ref "I2C-1") (pin "1") (pinfunction "1_1") (pintype "passive"))
      (node (ref "I2C-2") (pin "1") (pinfunction "1_1") (pintype "passive"))
      (node (ref "I2C-3") (pin "1") (pinfunction "1_1") (pintype "passive"))
      (node (ref "I2C-3") (pin "2") (pinfunction "2_2") (pintype "passive"))
      (node (ref "I2C-4") (pin "1") (pinfunction "1_1") (pintype "passive"))
      (node (ref "IC2") (pin "2") (pinfunction "VOUT_2") (pintype "output"))
      (node (ref "JP14") (pin "2") (pinfunction "2_2") (pintype "passive"))
      (node (ref "M1") (pin "J6.4") (pinfunction "VCC_J6.4") (pintype "power_in"))
      (node (ref "MOTION") (pin "1") (pinfunction "1_1") (pintype "passive"))
      (node (ref "R3") (pin "1") (pinfunction "1_1") (pintype "passive"))
      (node (ref "R5") (pin "1") (pinfunction "1_1") (pintype "passive"))
      (node (ref "R7") (pin "1") (pinfunction "1_1") (pintype "passive"))
      (node (ref "R8") (pin "2") (pinfunction "2_2") (pintype "passive"))
      (node (ref "RFM69W") (pin "VCC") (pinfunction "VCC_VCC") (pintype "bidirectional"))
      (node (ref "RS485") (pin "8") (pinfunction "VCC_8") (pintype "power_in"))
      (node (ref "RS485-") (pin "1") (pinfunction "1_1") (pintype "passive"))
      (node (ref "STEPDWN") (pin "1") (pinfunction "1_1") (pintype "passive"))
      (node (ref "STEPDWN") (pin "4") (pinfunction "4_4") (pintype "passive"))
      (node (ref "SV1") (pin "2") (pinfunction "2_2") (pintype "passive"))
      (node (ref "SV1") (pin "3") (pinfunction "3_3") (pintype "passive"))
      (node (ref "U1") (pin "3.3V") (pinfunction "3.3V_3.3V") (pintype "power_in"))
      (node (ref "X1") (pin "1") (pinfunction "K_1") (pintype "passive"))
      (node (ref "X4") (pin "1") (pinfunction "K_1") (pintype "passive"))
    )
    (net (code "41") (name "unconnected-(CC0-PadGDO2)") (class "Default")
      (node (ref "CC0") (pin "GDO2") (pinfunction "GDO2_GDO2") (pintype "bidirectional"))
    )
    (net (code "42") (name "unconnected-(J1A-S1-PadG3)") (class "Default")
      (node (ref "J1") (pin "G3") (pinfunction "S1_G3") (pintype "passive"))
    )
    (net (code "43") (name "unconnected-(J1A-S2-PadG1)") (class "Default")
      (node (ref "J1") (pin "G1") (pinfunction "S2_G1") (pintype "passive"))
    )
    (net (code "44") (name "unconnected-(J1B-4-Pad2-4)") (class "Default")
      (node (ref "J1") (pin "2-4") (pinfunction "4_2-4") (pintype "passive"))
    )
    (net (code "45") (name "unconnected-(J1B-5-Pad2-5)") (class "Default")
      (node (ref "J1") (pin "2-5") (pinfunction "5_2-5") (pintype "passive"))
    )
    (net (code "46") (name "unconnected-(JP2-Pad1)") (class "Default")
      (node (ref "JP2") (pin "1") (pinfunction "1_1") (pintype "passive"))
    )
    (net (code "47") (name "unconnected-(JP2-Pad2)") (class "Default")
      (node (ref "JP2") (pin "2") (pinfunction "2_2") (pintype "passive"))
    )
    (net (code "48") (name "unconnected-(JP2-Pad3)") (class "Default")
      (node (ref "JP2") (pin "3") (pinfunction "3_3") (pintype "passive"))
    )
    (net (code "49") (name "unconnected-(JP2-Pad4)") (class "Default")
      (node (ref "JP2") (pin "4") (pinfunction "4_4") (pintype "passive"))
    )
    (net (code "50") (name "unconnected-(JP4-Pad1)") (class "Default")
      (node (ref "JP4") (pin "1") (pinfunction "1_1") (pintype "passive"))
    )
    (net (code "51") (name "unconnected-(JP4-Pad2)") (class "Default")
      (node (ref "JP4") (pin "2") (pinfunction "2_2") (pintype "passive"))
    )
    (net (code "52") (name "unconnected-(JP4-Pad3)") (class "Default")
      (node (ref "JP4") (pin "3") (pinfunction "3_3") (pintype "passive"))
    )
    (net (code "53") (name "unconnected-(JP4-Pad4)") (class "Default")
      (node (ref "JP4") (pin "4") (pinfunction "4_4") (pintype "passive"))
    )
    (net (code "54") (name "unconnected-(JP5-Pad1)") (class "Default")
      (node (ref "JP5") (pin "1") (pinfunction "1_1") (pintype "passive"))
    )
    (net (code "55") (name "unconnected-(JP5-Pad2)") (class "Default")
      (node (ref "JP5") (pin "2") (pinfunction "2_2") (pintype "passive"))
    )
    (net (code "56") (name "unconnected-(JP5-Pad3)") (class "Default")
      (node (ref "JP5") (pin "3") (pinfunction "3_3") (pintype "passive"))
    )
    (net (code "57") (name "unconnected-(JP5-Pad4)") (class "Default")
      (node (ref "JP5") (pin "4") (pinfunction "4_4") (pintype "passive"))
    )
    (net (code "58") (name "unconnected-(JP6-Pad1)") (class "Default")
      (node (ref "JP6") (pin "1") (pinfunction "1_1") (pintype "passive"))
    )
    (net (code "59") (name "unconnected-(JP6-Pad2)") (class "Default")
      (node (ref "JP6") (pin "2") (pinfunction "2_2") (pintype "passive"))
    )
    (net (code "60") (name "unconnected-(JP6-Pad3)") (class "Default")
      (node (ref "JP6") (pin "3") (pinfunction "3_3") (pintype "passive"))
    )
    (net (code "61") (name "unconnected-(JP6-Pad4)") (class "Default")
      (node (ref "JP6") (pin "4") (pinfunction "4_4") (pintype "passive"))
    )
    (net (code "62") (name "unconnected-(JP7-Pad1)") (class "Default")
      (node (ref "JP7") (pin "1") (pinfunction "1_1") (pintype "passive"))
    )
    (net (code "63") (name "unconnected-(JP7-Pad2)") (class "Default")
      (node (ref "JP7") (pin "2") (pinfunction "2_2") (pintype "passive"))
    )
    (net (code "64") (name "unconnected-(JP7-Pad3)") (class "Default")
      (node (ref "JP7") (pin "3") (pinfunction "3_3") (pintype "passive"))
    )
    (net (code "65") (name "unconnected-(JP7-Pad4)") (class "Default")
      (node (ref "JP7") (pin "4") (pinfunction "4_4") (pintype "passive"))
    )
    (net (code "66") (name "unconnected-(JP8-Pad1)") (class "Default")
      (node (ref "JP8") (pin "1") (pinfunction "1_1") (pintype "passive"))
    )
    (net (code "67") (name "unconnected-(JP8-Pad2)") (class "Default")
      (node (ref "JP8") (pin "2") (pinfunction "2_2") (pintype "passive"))
    )
    (net (code "68") (name "unconnected-(JP8-Pad3)") (class "Default")
      (node (ref "JP8") (pin "3") (pinfunction "3_3") (pintype "passive"))
    )
    (net (code "69") (name "unconnected-(JP8-Pad4)") (class "Default")
      (node (ref "JP8") (pin "4") (pinfunction "4_4") (pintype "passive"))
    )
    (net (code "70") (name "unconnected-(JP9-Pad1)") (class "Default")
      (node (ref "JP9") (pin "1") (pinfunction "1_1") (pintype "passive"))
    )
    (net (code "71") (name "unconnected-(JP9-Pad2)") (class "Default")
      (node (ref "JP9") (pin "2") (pinfunction "2_2") (pintype "passive"))
    )
    (net (code "72") (name "unconnected-(JP9-Pad3)") (class "Default")
      (node (ref "JP9") (pin "3") (pinfunction "3_3") (pintype "passive"))
    )
    (net (code "73") (name "unconnected-(JP9-Pad4)") (class "Default")
      (node (ref "JP9") (pin "4") (pinfunction "4_4") (pintype "passive"))
    )
    (net (code "74") (name "unconnected-(JP10-Pad1)") (class "Default")
      (node (ref "JP10") (pin "1") (pinfunction "1_1") (pintype "passive"))
    )
    (net (code "75") (name "unconnected-(JP10-Pad2)") (class "Default")
      (node (ref "JP10") (pin "2") (pinfunction "2_2") (pintype "passive"))
    )
    (net (code "76") (name "unconnected-(JP10-Pad3)") (class "Default")
      (node (ref "JP10") (pin "3") (pinfunction "3_3") (pintype "passive"))
    )
    (net (code "77") (name "unconnected-(JP10-Pad4)") (class "Default")
      (node (ref "JP10") (pin "4") (pinfunction "4_4") (pintype "passive"))
    )
    (net (code "78") (name "unconnected-(JP11-Pad1)") (class "Default")
      (node (ref "JP11") (pin "1") (pinfunction "1_1") (pintype "passive"))
    )
    (net (code "79") (name "unconnected-(JP11-Pad2)") (class "Default")
      (node (ref "JP11") (pin "2") (pinfunction "2_2") (pintype "passive"))
    )
    (net (code "80") (name "unconnected-(JP11-Pad3)") (class "Default")
      (node (ref "JP11") (pin "3") (pinfunction "3_3") (pintype "passive"))
    )
    (net (code "81") (name "unconnected-(JP11-Pad4)") (class "Default")
      (node (ref "JP11") (pin "4") (pinfunction "4_4") (pintype "passive"))
    )
    (net (code "82") (name "unconnected-(JP12-Pad1)") (class "Default")
      (node (ref "JP12") (pin "1") (pinfunction "1_1") (pintype "passive"))
    )
    (net (code "83") (name "unconnected-(JP12-Pad2)") (class "Default")
      (node (ref "JP12") (pin "2") (pinfunction "2_2") (pintype "passive"))
    )
    (net (code "84") (name "unconnected-(JP12-Pad3)") (class "Default")
      (node (ref "JP12") (pin "3") (pinfunction "3_3") (pintype "passive"))
    )
    (net (code "85") (name "unconnected-(JP12-Pad4)") (class "Default")
      (node (ref "JP12") (pin "4") (pinfunction "4_4") (pintype "passive"))
    )
    (net (code "86") (name "unconnected-(JP13-Pad1)") (class "Default")
      (node (ref "JP13") (pin "1") (pinfunction "1_1") (pintype "passive"))
    )
    (net (code "87") (name "unconnected-(JP13-Pad2)") (class "Default")
      (node (ref "JP13") (pin "2") (pinfunction "2_2") (pintype "passive"))
    )
    (net (code "88") (name "unconnected-(JP13-Pad3)") (class "Default")
      (node (ref "JP13") (pin "3") (pinfunction "3_3") (pintype "passive"))
    )
    (net (code "89") (name "unconnected-(JP13-Pad4)") (class "Default")
      (node (ref "JP13") (pin "4") (pinfunction "4_4") (pintype "passive"))
    )
    (net (code "90") (name "unconnected-(M1-RST.1-PadJ6.3)") (class "Default")
      (node (ref "M1") (pin "J6.3") (pinfunction "RST.1_J6.3") (pintype "bidirectional"))
    )
    (net (code "91") (name "unconnected-(RFM69W-PadDIO1)") (class "Default")
      (node (ref "RFM69W") (pin "DIO1") (pinfunction "DIO1_DIO1") (pintype "bidirectional"))
    )
    (net (code "92") (name "unconnected-(RFM69W-PadDIO2)") (class "Default")
      (node (ref "RFM69W") (pin "DIO2") (pinfunction "DIO2_DIO2") (pintype "bidirectional"))
    )
    (net (code "93") (name "unconnected-(RFM69W-PadDIO3)") (class "Default")
      (node (ref "RFM69W") (pin "DIO3") (pinfunction "DIO3_DIO3") (pintype "bidirectional"))
    )
    (net (code "94") (name "unconnected-(RFM69W-PadDIO4)") (class "Default")
      (node (ref "RFM69W") (pin "DIO4") (pinfunction "DIO4_DIO4") (pintype "bidirectional"))
    )
    (net (code "95") (name "unconnected-(RFM69W-PadDIO5)") (class "Default")
      (node (ref "RFM69W") (pin "DIO5") (pinfunction "DIO5_DIO5") (pintype "bidirectional"))
    )
    (net (code "96") (name "unconnected-(RFM69W-PadNC)") (class "Default")
      (node (ref "RFM69W") (pin "NC") (pinfunction "NC_NC") (pintype "bidirectional"))
    )
    (net (code "97") (name "unconnected-(RFM69W-PadRESET)") (class "Default")
      (node (ref "RFM69W") (pin "RESET") (pinfunction "RESET_RESET") (pintype "bidirectional"))
    )
    (net (code "98") (name "unconnected-(U1-PadDIO1)") (class "Default")
      (node (ref "U1") (pin "DIO1") (pinfunction "DIO1_DIO1") (pintype "bidirectional"))
    )
    (net (code "99") (name "unconnected-(U1-PadDIO2)") (class "Default")
      (node (ref "U1") (pin "DIO2") (pinfunction "DIO2_DIO2") (pintype "bidirectional"))
    )
    (net (code "100") (name "unconnected-(U1-PadRESET)") (class "Default")
      (node (ref "U1") (pin "RESET") (pinfunction "RESET_RESET") (pintype "input"))
    )
  )
)
